# SIO-XS_v1p1.net
KiCad netlist of a schematic drawn in EAGLE
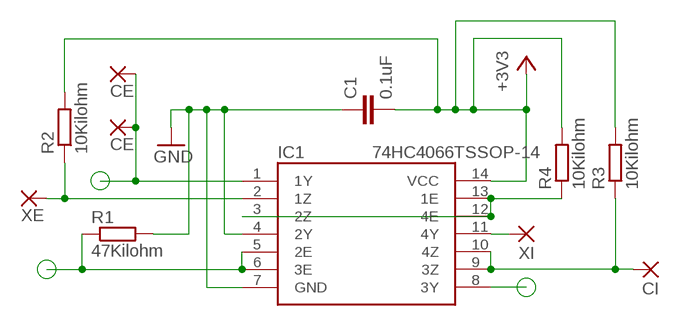
[diagram p0: schematic, sheet 1]

(export (version "E")
  (design (tool "Eeschema 10.0.6"))
  (components
    (comp (ref "C1")
      (value "0.1uF")
      (footprint "eagle-import:C0805")
      (libsource (lib "eagle-import") (part "CAPACITORSC0805"))
    )
    (comp (ref "CE")
      (value "CE")
      (footprint "eagle-import:CIRCLE-1,5X1,5")
      (libsource (lib "eagle-import") (part "PADSCIRCLE-1,5X1,5"))
    )
    (comp (ref "CE1")
      (value "CE")
      (footprint "eagle-import:CIRCLE-1,5X1,5")
      (libsource (lib "eagle-import") (part "PADSCIRCLE-1,5X1,5"))
    )
    (comp (ref "CI")
      (value "CI")
      (footprint "eagle-import:CIRCLE-1,5X1,5")
      (libsource (lib "eagle-import") (part "PADSCIRCLE-1,5X1,5"))
    )
    (comp (ref "IC1")
      (value "74HC4066TSSOP-14")
      (footprint "eagle-import:TSSOP-14")
      (libsource (lib "eagle-import") (part "74HC4066TSSOP-14"))
    )
    (comp (ref "R1")
      (value "47Kilohm")
      (footprint "eagle-import:R0805")
      (libsource (lib "eagle-import") (part "RESISTORSR0805"))
    )
    (comp (ref "R2")
      (value "10Kilohm")
      (footprint "eagle-import:R0805")
      (libsource (lib "eagle-import") (part "RESISTORSR0805"))
    )
    (comp (ref "R3")
      (value "10Kilohm")
      (footprint "eagle-import:R0805")
      (libsource (lib "eagle-import") (part "RESISTORSR0805"))
    )
    (comp (ref "R4")
      (value "10Kilohm")
      (footprint "eagle-import:R0805")
      (libsource (lib "eagle-import") (part "RESISTORSR0805"))
    )
    (comp (ref "XE")
      (value "XE")
      (footprint "eagle-import:CIRCLE-1,5X1,5")
      (libsource (lib "eagle-import") (part "PADSCIRCLE-1,5X1,5"))
    )
    (comp (ref "XI")
      (value "XI")
      (footprint "eagle-import:CIRCLE-1,5X1,5")
      (libsource (lib "eagle-import") (part "PADSCIRCLE-1,5X1,5"))
    )
  )
  (nets
    (net (code "1") (name "+3V3") (class "Default")
      (node (ref "C1") (pin "2") (pinfunction "2_2") (pintype "passive"))
      (node (ref "IC1") (pin "14") (pinfunction "VCC_14") (pintype "bidirectional"))
      (node (ref "R2") (pin "2") (pinfunction "2_2") (pintype "passive"))
      (node (ref "R3") (pin "2") (pinfunction "2_2") (pintype "passive"))
      (node (ref "R4") (pin "2") (pinfunction "2_2") (pintype "passive"))
    )
    (net (code "2") (name "GND") (class "Default")
      (node (ref "C1") (pin "1") (pinfunction "1_1") (pintype "passive"))
      (node (ref "IC1") (pin "4") (pinfunction "2Y_4") (pintype "bidirectional"))
      (node (ref "IC1") (pin "7") (pinfunction "GND_7") (pintype "bidirectional"))
      (node (ref "R1") (pin "2") (pinfunction "2_2") (pintype "passive"))
    )
    (net (code "3") (name "Net-(CE-P)") (class "Default")
      (node (ref "CE") (pin "1") (pinfunction "P_1") (pintype "passive"))
      (node (ref "CE1") (pin "1") (pinfunction "P_1") (pintype "passive"))
      (node (ref "IC1") (pin "1") (pinfunction "1Y_1") (pintype "bidirectional"))
    )
    (net (code "4") (name "Net-(CI-P)") (class "Default")
      (node (ref "CI") (pin "1") (pinfunction "P_1") (pintype "passive"))
      (node (ref "IC1") (pin "10") (pinfunction "4Z_10") (pintype "bidirectional"))
      (node (ref "IC1") (pin "9") (pinfunction "3Z_9") (pintype "bidirectional"))
      (node (ref "R3") (pin "1") (pinfunction "1_1") (pintype "passive"))
    )
    (net (code "5") (name "Net-(IC1-1E)") (class "Default")
      (node (ref "IC1") (pin "12") (pinfunction "4E_12") (pintype "bidirectional"))
      (node (ref "IC1") (pin "13") (pinfunction "1E_13") (pintype "bidirectional"))
      (node (ref "IC1") (pin "3") (pinfunction "2Z_3") (pintype "bidirectional"))
      (node (ref "R4") (pin "1") (pinfunction "1_1") (pintype "passive"))
    )
    (net (code "6") (name "Net-(IC1-1Z)") (class "Default")
      (node (ref "IC1") (pin "2") (pinfunction "1Z_2") (pintype "bidirectional"))
      (node (ref "R2") (pin "1") (pinfunction "1_1") (pintype "passive"))
      (node (ref "XE") (pin "1") (pinfunction "P_1") (pintype "passive"))
    )
    (net (code "7") (name "Net-(IC1-2E)") (class "Default")
      (node (ref "IC1") (pin "5") (pinfunction "2E_5") (pintype "bidirectional"))
      (node (ref "IC1") (pin "6") (pinfunction "3E_6") (pintype "bidirectional"))
      (node (ref "R1") (pin "1") (pinfunction "1_1") (pintype "passive"))
    )
    (net (code "8") (name "Net-(IC1-4Y)") (class "Default")
      (node (ref "IC1") (pin "11") (pinfunction "4Y_11") (pintype "bidirectional"))
      (node (ref "XI") (pin "1") (pinfunction "P_1") (pintype "passive"))
    )
    (net (code "9") (name "unconnected-(IC1-3Y-Pad8)") (class "Default")
      (node (ref "IC1") (pin "8") (pinfunction "3Y_8") (pintype "bidirectional"))
    )
  )
)
